# 04_Power_Supply.net
KiCad netlist of a schematic drawn in Altium Designer
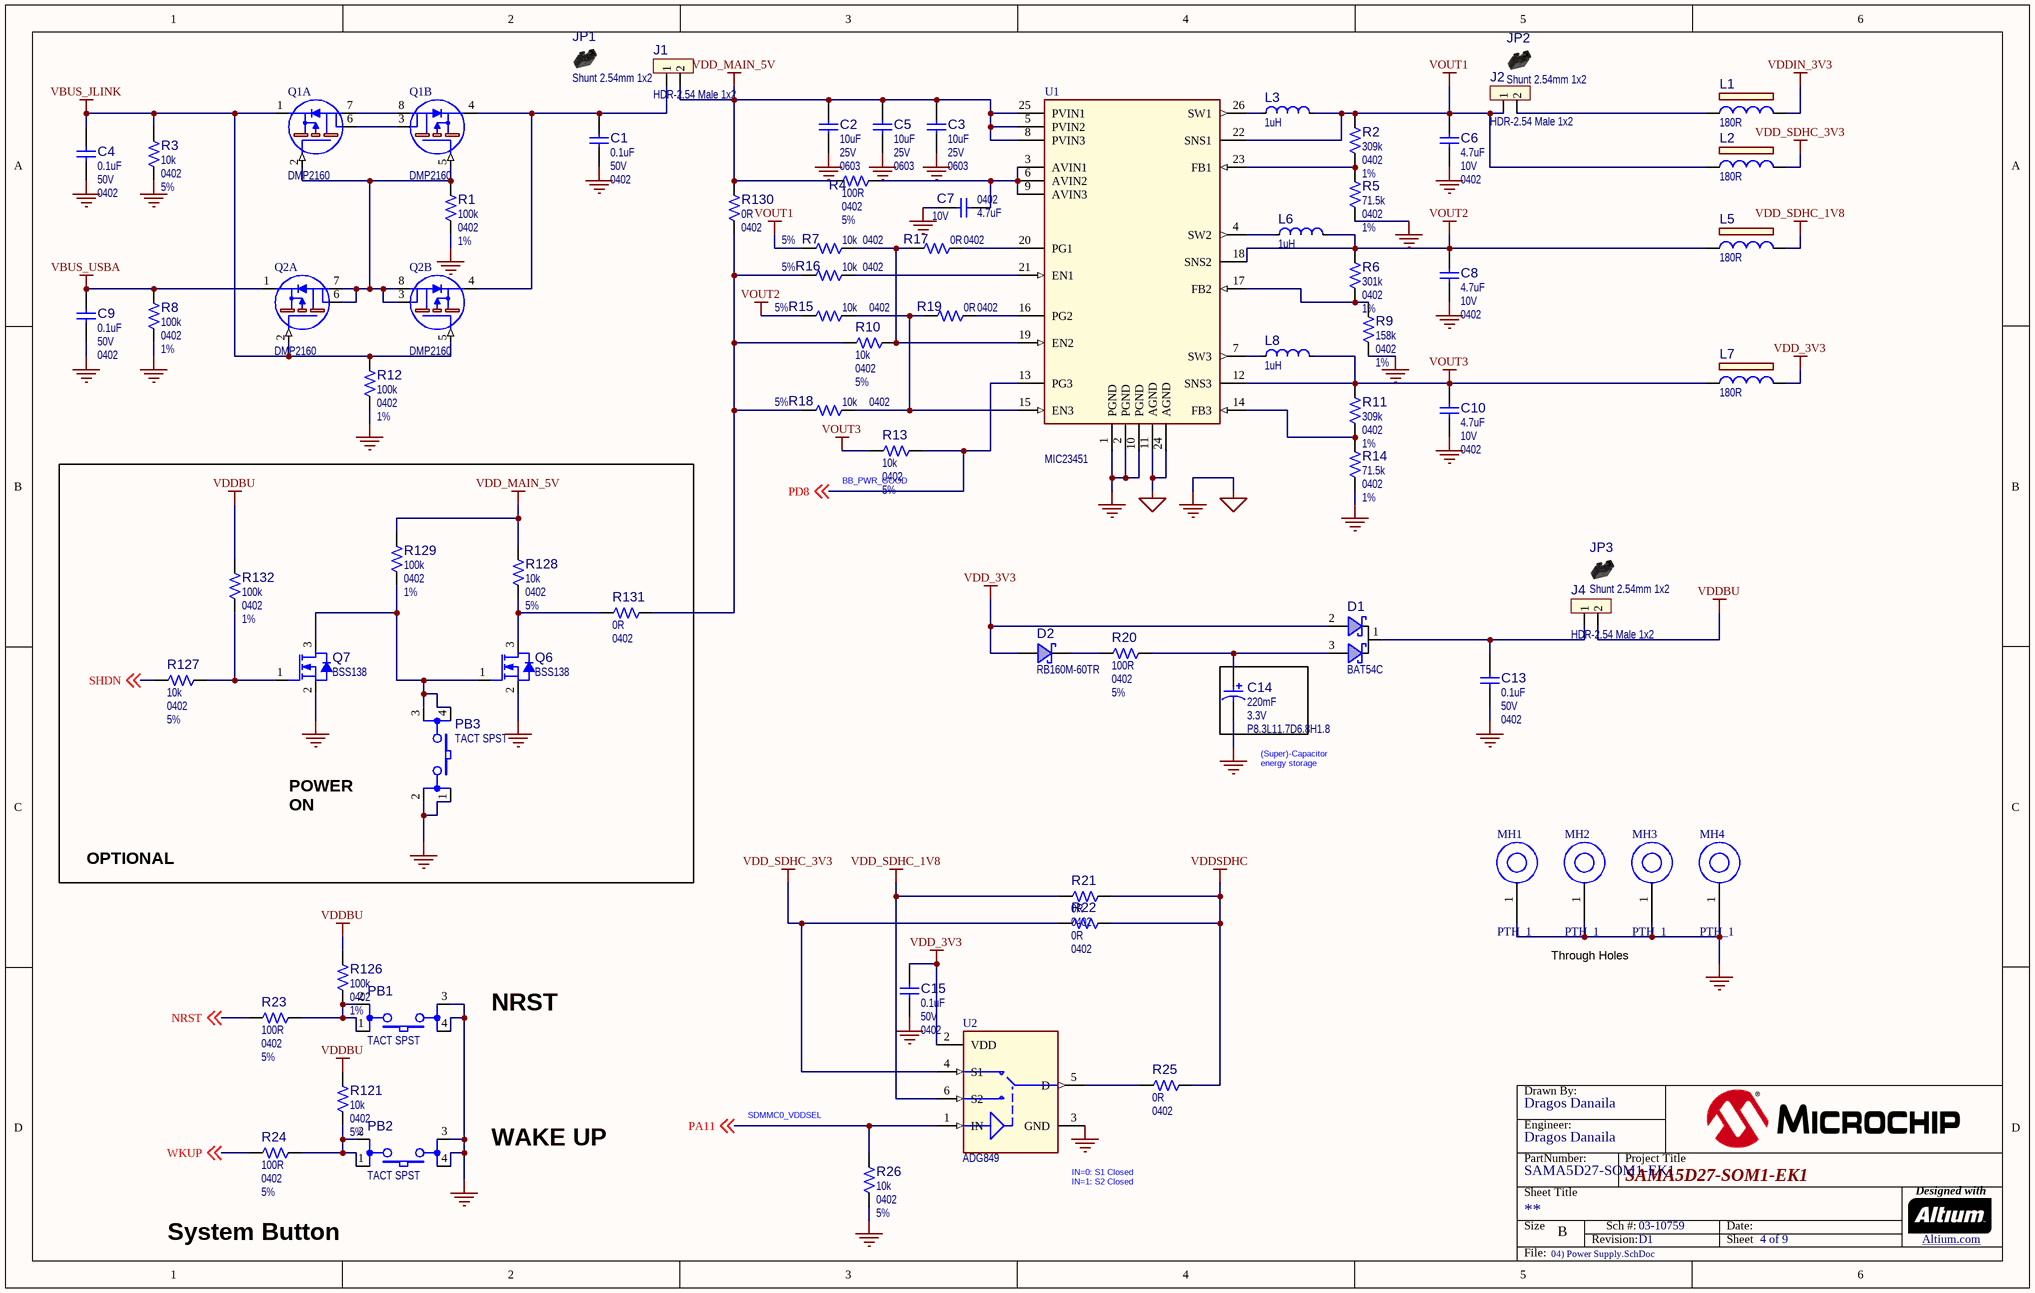
[diagram p0: 04) Power Supply.SchDoc]

(export (version "E")
  (design (tool "Eeschema 10.0.6"))
  (components
    (comp (ref "C1")
      (value "0.1uF")
      (footprint "CAP_C_0402")
      (description "Capacitor")
      (fields
        (field (name "VOLTAGE") "50V")
        (field (name "PACKAGE") "0402")
        (field (name "TOLERANCE") "10%")
        (field (name "Comment") "Capacitor NP")
        (field (name "OWNER") "Jamus Griego")
      )
      (libsource (lib "MCHP-CDB") (part "Capacitor NP"))
    )
    (comp (ref "C2")
      (value "10uF")
      (footprint "CAP_C_0603")
      (description "Capacitor")
      (fields
        (field (name "VOLTAGE") "25V")
        (field (name "PACKAGE") "0603")
        (field (name "TOLERANCE") "20%")
        (field (name "Comment") "Capacitor NP")
        (field (name "OWNER") "Razvan Cristescu")
      )
      (libsource (lib "MCHP-CDB") (part "Capacitor NP"))
    )
    (comp (ref "C3")
      (value "10uF")
      (footprint "CAP_C_0603")
      (description "Capacitor")
      (fields
        (field (name "VOLTAGE") "25V")
        (field (name "PACKAGE") "0603")
        (field (name "TOLERANCE") "20%")
        (field (name "Comment") "Capacitor NP")
        (field (name "OWNER") "Razvan Cristescu")
      )
      (libsource (lib "MCHP-CDB") (part "Capacitor NP"))
    )
    (comp (ref "C4")
      (value "0.1uF")
      (footprint "CAP_C_0402")
      (description "Capacitor")
      (fields
        (field (name "VOLTAGE") "50V")
        (field (name "PACKAGE") "0402")
        (field (name "TOLERANCE") "10%")
        (field (name "Comment") "Capacitor NP")
        (field (name "OWNER") "Jamus Griego")
      )
      (libsource (lib "MCHP-CDB") (part "Capacitor NP"))
    )
    (comp (ref "C5")
      (value "10uF")
      (footprint "CAP_C_0603")
      (description "Capacitor")
      (fields
        (field (name "VOLTAGE") "25V")
        (field (name "PACKAGE") "0603")
        (field (name "TOLERANCE") "20%")
        (field (name "Comment") "Capacitor NP")
        (field (name "OWNER") "Razvan Cristescu")
      )
      (libsource (lib "MCHP-CDB") (part "Capacitor NP"))
    )
    (comp (ref "C6")
      (value "4.7uF")
      (footprint "CAP_C_0402")
      (description "Capacitor")
      (fields
        (field (name "VOLTAGE") "10V")
        (field (name "PACKAGE") "0402")
        (field (name "TOLERANCE") "10%")
        (field (name "Comment") "Capacitor NP")
        (field (name "OWNER") "Jesus Aviles")
      )
      (libsource (lib "MCHP-CDB") (part "Capacitor NP"))
    )
    (comp (ref "C7")
      (value "4.7uF")
      (footprint "CAP_C_0402")
      (description "Capacitor")
      (fields
        (field (name "VOLTAGE") "10V")
        (field (name "PACKAGE") "0402")
        (field (name "TOLERANCE") "10%")
        (field (name "Comment") "Capacitor NP")
        (field (name "OWNER") "Jesus Aviles")
      )
      (libsource (lib "MCHP-CDB") (part "Capacitor NP"))
    )
    (comp (ref "C8")
      (value "4.7uF")
      (footprint "CAP_C_0402")
      (description "Capacitor")
      (fields
        (field (name "VOLTAGE") "10V")
        (field (name "PACKAGE") "0402")
        (field (name "TOLERANCE") "10%")
        (field (name "Comment") "Capacitor NP")
        (field (name "OWNER") "Jesus Aviles")
      )
      (libsource (lib "MCHP-CDB") (part "Capacitor NP"))
    )
    (comp (ref "C9")
      (value "0.1uF")
      (footprint "CAP_C_0402")
      (description "Capacitor")
      (fields
        (field (name "VOLTAGE") "50V")
        (field (name "PACKAGE") "0402")
        (field (name "TOLERANCE") "10%")
        (field (name "Comment") "Capacitor NP")
        (field (name "OWNER") "Jamus Griego")
      )
      (libsource (lib "MCHP-CDB") (part "Capacitor NP"))
    )
    (comp (ref "C10")
      (value "4.7uF")
      (footprint "CAP_C_0402")
      (description "Capacitor")
      (fields
        (field (name "VOLTAGE") "10V")
        (field (name "PACKAGE") "0402")
        (field (name "TOLERANCE") "10%")
        (field (name "Comment") "Capacitor NP")
        (field (name "OWNER") "Jesus Aviles")
      )
      (libsource (lib "MCHP-CDB") (part "Capacitor NP"))
    )
    (comp (ref "C13")
      (value "0.1uF")
      (footprint "CAP_C_0402")
      (description "Capacitor")
      (fields
        (field (name "VOLTAGE") "50V")
        (field (name "PACKAGE") "0402")
        (field (name "TOLERANCE") "10%")
        (field (name "Comment") "Capacitor NP")
        (field (name "OWNER") "Jamus Griego")
      )
      (libsource (lib "MCHP-CDB") (part "Capacitor NP"))
    )
    (comp (ref "C14")
      (value "220mF")
      (footprint "CAP_AX_P8.3L11.7D6.8H1.8")
      (description "Capacitor")
      (fields
        (field (name "VOLTAGE") "3.3V")
        (field (name "PACKAGE") "P8.3L11.7D6.8H1.8")
        (field (name "TOLERANCE") "-20%, +80%")
        (field (name "Comment") "Capacitor POL")
        (field (name "OWNER") "Alexandru Chiser - M19201")
      )
      (libsource (lib "MCHP-CDB") (part "Capacitor POL"))
    )
    (comp (ref "C15")
      (value "0.1uF")
      (footprint "CAP_C_0402")
      (description "Capacitor")
      (fields
        (field (name "VOLTAGE") "50V")
        (field (name "PACKAGE") "0402")
        (field (name "TOLERANCE") "10%")
        (field (name "Comment") "Capacitor NP")
        (field (name "OWNER") "Jamus Griego")
      )
      (libsource (lib "MCHP-CDB") (part "Capacitor NP"))
    )
    (comp (ref "D1")
      (value "BAT54C")
      (footprint "SOT-23-3_REVERSED")
      (fields (field (name "POWER") "330mW") (field (name "Comment") "Diode Schottky Dual CK-1"))
      (libsource (lib "MCHP-CDB") (part "Diode Schottky Dual CK-1"))
    )
    (comp (ref "D2")
      (value "RB160M-60TR")
      (footprint "SOD-123FL")
      (description "DIO SCTKY RB160M-60TR 550mV 1A 60V SMD SOD-123F")
      (fields
        (field (name "POWER") "1W")
        (field (name "Comment") "Diode Schottky")
        (field (name "OWNER") "Dragos Danaila")
      )
      (libsource (lib "MCHP-CDB") (part "Diode Schottky"))
    )
    (comp (ref "J1")
      (value "HDR-2.54 Male 1x2")
      (footprint "HDR_M_2.54_1x2")
      (fields (field (name "Comment") "Header 1x2") (field (name "OWNER") "Bogdan P (M91398)"))
      (libsource (lib "MCHP-CDB") (part "Header 1x2"))
    )
    (comp (ref "J2")
      (value "HDR-2.54 Male 1x2")
      (footprint "HDR_M_2.54_1x2")
      (fields (field (name "Comment") "Header 1x2") (field (name "OWNER") "Bogdan P (M91398)"))
      (libsource (lib "MCHP-CDB") (part "Header 1x2"))
    )
    (comp (ref "J4")
      (value "HDR-2.54 Male 1x2")
      (footprint "HDR_M_2.54_1x2")
      (fields (field (name "Comment") "Header 1x2") (field (name "OWNER") "Bogdan P (M91398)"))
      (libsource (lib "MCHP-CDB") (part "Header 1x2"))
    )
    (comp (ref "JP1")
      (value "Shunt 2.54mm 1x2")
      (footprint "Jumper_Mechanical")
      (fields (field (name "Comment") "Jumper Mechanical") (field (name "OWNER") "Mike Ragsdale"))
      (libsource (lib "MCHP-CDB") (part "Jumper Mechanical"))
    )
    (comp (ref "JP2")
      (value "Shunt 2.54mm 1x2")
      (footprint "Jumper_Mechanical")
      (fields (field (name "Comment") "Jumper Mechanical") (field (name "OWNER") "Mike Ragsdale"))
      (libsource (lib "MCHP-CDB") (part "Jumper Mechanical"))
    )
    (comp (ref "JP3")
      (value "Shunt 2.54mm 1x2")
      (footprint "Jumper_Mechanical")
      (fields (field (name "Comment") "Jumper Mechanical") (field (name "OWNER") "Mike Ragsdale"))
      (libsource (lib "MCHP-CDB") (part "Jumper Mechanical"))
    )
    (comp (ref "L1")
      (value "180R")
      (footprint "IND_C_0603")
      (description "FERRITE 180R 1.5A SMD 0603")
      (fields (field (name "Comment") "Ferrite Bead") (field (name "OWNER") "Dragos Danaila"))
      (libsource (lib "MCHP-CDB") (part "Ferrite Bead"))
    )
    (comp (ref "L2")
      (value "180R")
      (footprint "IND_C_0603")
      (description "FERRITE 180R 1.5A SMD 0603")
      (fields (field (name "Comment") "Ferrite Bead") (field (name "OWNER") "Dragos Danaila"))
      (libsource (lib "MCHP-CDB") (part "Ferrite Bead"))
    )
    (comp (ref "L3")
      (value "1uH")
      (footprint "IND_C_1210")
      (description "Inductor")
      (fields (field (name "OWNER") "Dragos Danaila"))
      (libsource (lib "MCHP-CDB") (part "Inductor"))
    )
    (comp (ref "L5")
      (value "180R")
      (footprint "IND_C_0603")
      (description "FERRITE 180R 1.5A SMD 0603")
      (fields (field (name "Comment") "Ferrite Bead") (field (name "OWNER") "Dragos Danaila"))
      (libsource (lib "MCHP-CDB") (part "Ferrite Bead"))
    )
    (comp (ref "L6")
      (value "1uH")
      (footprint "IND_C_1210")
      (description "Inductor")
      (fields (field (name "OWNER") "Dragos Danaila"))
      (libsource (lib "MCHP-CDB") (part "Inductor"))
    )
    (comp (ref "L7")
      (value "180R")
      (footprint "IND_C_0603")
      (description "FERRITE 180R 1.5A SMD 0603")
      (fields (field (name "Comment") "Ferrite Bead") (field (name "OWNER") "Dragos Danaila"))
      (libsource (lib "MCHP-CDB") (part "Ferrite Bead"))
    )
    (comp (ref "L8")
      (value "1uH")
      (footprint "IND_C_1210")
      (description "Inductor")
      (fields (field (name "OWNER") "Dragos Danaila"))
      (libsource (lib "MCHP-CDB") (part "Inductor"))
    )
    (comp (ref "MH1")
      (value "PTH_1")
      (footprint "ATM1099C-0627-ssy-1.brd:HOLE2")
      (libsource (lib "SAMA5D27-SOM1-EK1_ REVB_Library") (part "PTH_1"))
    )
    (comp (ref "MH2")
      (value "PTH_1")
      (footprint "ATM1099C-0627-ssy-1.brd:HOLE2")
      (libsource (lib "SAMA5D27-SOM1-EK1_ REVB_Library") (part "PTH_1"))
    )
    (comp (ref "MH3")
      (value "PTH_1")
      (footprint "ATM1099C-0627-ssy-1.brd:HOLE2")
      (libsource (lib "SAMA5D27-SOM1-EK1_ REVB_Library") (part "PTH_1"))
    )
    (comp (ref "MH4")
      (value "PTH_1")
      (footprint "ATM1099C-0627-ssy-1.brd:HOLE2")
      (libsource (lib "SAMA5D27-SOM1-EK1_ REVB_Library") (part "PTH_1"))
    )
    (comp (ref "PB1")
      (value "TACT SPST")
      (footprint "SW_SMD_6mmX6mm_TL3301")
      (description "Switch")
      (fields (field (name "VOLTAGE") "12V") (field (name "Comment") "Switch 4 Pin"))
      (libsource (lib "MCHP-CDB") (part "Switch 4 Pin"))
    )
    (comp (ref "PB2")
      (value "TACT SPST")
      (footprint "SW_SMD_6mmX6mm_TL3301")
      (description "Switch")
      (fields (field (name "VOLTAGE") "12V") (field (name "Comment") "Switch 4 Pin"))
      (libsource (lib "MCHP-CDB") (part "Switch 4 Pin"))
    )
    (comp (ref "PB3")
      (value "TACT SPST")
      (footprint "SW_SMD_6mmX6mm_TL3301")
      (description "Switch")
      (fields (field (name "VOLTAGE") "12V") (field (name "Comment") "Switch 4 Pin"))
      (libsource (lib "MCHP-CDB") (part "Switch 4 Pin"))
    )
    (comp (ref "Q1")
      (value "DMP2160")
      (footprint "U-DFN2020-6_2.0x2.0")
      (description "Dual P-Channel MOSFET")
      (fields
        (field (name "POWER") "1.4W")
        (field (name "VOLTAGE") "20V")
        (field (name "OWNER") "Dragos Danaila")
      )
      (libsource (lib "") (part "Transistor U-DFN2020-6-SGDSGD_1"))
    )
    (comp (ref "Q2")
      (value "DMP2160")
      (footprint "U-DFN2020-6_2.0x2.0")
      (description "Dual P-Channel MOSFET")
      (fields
        (field (name "POWER") "1.4W")
        (field (name "VOLTAGE") "20V")
        (field (name "OWNER") "Dragos Danaila")
      )
      (libsource (lib "MCHP-CDB") (part "Transistor U-DFN2020-6-SGDSGD"))
    )
    (comp (ref "Q6")
      (value "BSS138")
      (footprint "SOT-23-3")
      (description "Transistor MOS")
      (fields
        (field (name "POWER") "360mW")
        (field (name "VOLTAGE") "50V")
        (field (name "OWNER") "Razvan Cristescu")
      )
      (libsource (lib "MCHP-CDB") (part "Transistor MOS-N GSD"))
    )
    (comp (ref "Q7")
      (value "BSS138")
      (footprint "SOT-23-3")
      (description "Transistor MOS")
      (fields
        (field (name "POWER") "360mW")
        (field (name "VOLTAGE") "50V")
        (field (name "OWNER") "Razvan Cristescu")
      )
      (libsource (lib "MCHP-CDB") (part "Transistor MOS-N GSD"))
    )
    (comp (ref "R1")
      (value "100k")
      (footprint "RES_C_0402")
      (description "Resistor")
      (fields
        (field (name "PACKAGE") "0402")
        (field (name "TOLERANCE") "1%")
        (field (name "VOLTAGE") "50V")
        (field (name "POWER") "1/10W")
        (field (name "OWNER") "Tad Ahlvers")
      )
      (libsource (lib "MCHP-CDB") (part "Resistor"))
    )
    (comp (ref "R2")
      (value "309k")
      (footprint "RES_C_0402")
      (description "Resistor")
      (fields
        (field (name "PACKAGE") "0402")
        (field (name "TOLERANCE") "1%")
        (field (name "VOLTAGE") "50V")
        (field (name "POWER") "1/16W")
        (field (name "OWNER") "Dragos Danaila")
      )
      (libsource (lib "MCHP-CDB") (part "Resistor"))
    )
    (comp (ref "R3")
      (value "10k")
      (footprint "RES_C_0402")
      (description "Resistor")
      (fields
        (field (name "PACKAGE") "0402")
        (field (name "TOLERANCE") "5%")
        (field (name "VOLTAGE") "50V")
        (field (name "POWER") "1/16W")
      )
      (libsource (lib "MCHP-CDB") (part "Resistor"))
    )
    (comp (ref "R4")
      (value "100R")
      (footprint "RES_C_0402")
      (description "Resistor")
      (fields
        (field (name "PACKAGE") "0402")
        (field (name "TOLERANCE") "5%")
        (field (name "VOLTAGE") "50V")
        (field (name "POWER") "1/16W")
        (field (name "OWNER") "Sompoch Loboonlert")
      )
      (libsource (lib "MCHP-CDB") (part "Resistor"))
    )
    (comp (ref "R5")
      (value "71.5k")
      (footprint "RES_C_0402")
      (description "Resistor")
      (fields
        (field (name "PACKAGE") "0402")
        (field (name "TOLERANCE") "1%")
        (field (name "VOLTAGE") "50V")
        (field (name "POWER") "1/16W")
        (field (name "OWNER") "Dragos Danaila")
      )
      (libsource (lib "MCHP-CDB") (part "Resistor"))
    )
    (comp (ref "R6")
      (value "301k")
      (footprint "RES_C_0402")
      (description "Resistor")
      (fields
        (field (name "PACKAGE") "0402")
        (field (name "TOLERANCE") "1%")
        (field (name "VOLTAGE") "50")
        (field (name "POWER") "1/16W")
        (field (name "OWNER") "Dragos Danaila")
      )
      (libsource (lib "MCHP-CDB") (part "Resistor"))
    )
    (comp (ref "R7")
      (value "10k")
      (footprint "RES_C_0402")
      (description "Resistor")
      (fields
        (field (name "PACKAGE") "0402")
        (field (name "TOLERANCE") "5%")
        (field (name "VOLTAGE") "50V")
        (field (name "POWER") "1/16W")
      )
      (libsource (lib "MCHP-CDB") (part "Resistor"))
    )
    (comp (ref "R8")
      (value "100k")
      (footprint "RES_C_0402")
      (description "Resistor")
      (fields
        (field (name "PACKAGE") "0402")
        (field (name "TOLERANCE") "1%")
        (field (name "VOLTAGE") "50V")
        (field (name "POWER") "1/10W")
        (field (name "OWNER") "Tad Ahlvers")
      )
      (libsource (lib "MCHP-CDB") (part "Resistor"))
    )
    (comp (ref "R9")
      (value "158k")
      (footprint "RES_C_0402")
      (description "Resistor")
      (fields
        (field (name "PACKAGE") "0402")
        (field (name "TOLERANCE") "1%")
        (field (name "VOLTAGE") "50V")
        (field (name "POWER") "1/16W")
        (field (name "OWNER") "Dragos Danaila")
      )
      (libsource (lib "MCHP-CDB") (part "Resistor"))
    )
    (comp (ref "R10")
      (value "10k")
      (footprint "RES_C_0402")
      (description "Resistor")
      (fields
        (field (name "PACKAGE") "0402")
        (field (name "TOLERANCE") "5%")
        (field (name "VOLTAGE") "50V")
        (field (name "POWER") "1/16W")
      )
      (libsource (lib "MCHP-CDB") (part "Resistor"))
    )
    (comp (ref "R11")
      (value "309k")
      (footprint "RES_C_0402")
      (description "Resistor")
      (fields
        (field (name "PACKAGE") "0402")
        (field (name "TOLERANCE") "1%")
        (field (name "VOLTAGE") "50V")
        (field (name "POWER") "1/16W")
        (field (name "OWNER") "Dragos Danaila")
      )
      (libsource (lib "MCHP-CDB") (part "Resistor"))
    )
    (comp (ref "R12")
      (value "100k")
      (footprint "RES_C_0402")
      (description "Resistor")
      (fields
        (field (name "PACKAGE") "0402")
        (field (name "TOLERANCE") "1%")
        (field (name "VOLTAGE") "50V")
        (field (name "POWER") "1/10W")
        (field (name "OWNER") "Tad Ahlvers")
      )
      (libsource (lib "MCHP-CDB") (part "Resistor"))
    )
    (comp (ref "R13")
      (value "10k")
      (footprint "RES_C_0402")
      (description "Resistor")
      (fields
        (field (name "PACKAGE") "0402")
        (field (name "TOLERANCE") "5%")
        (field (name "VOLTAGE") "50V")
        (field (name "POWER") "1/16W")
      )
      (libsource (lib "MCHP-CDB") (part "Resistor"))
    )
    (comp (ref "R14")
      (value "71.5k")
      (footprint "RES_C_0402")
      (description "Resistor")
      (fields
        (field (name "PACKAGE") "0402")
        (field (name "TOLERANCE") "1%")
        (field (name "VOLTAGE") "50V")
        (field (name "POWER") "1/16W")
        (field (name "OWNER") "Dragos Danaila")
      )
      (libsource (lib "MCHP-CDB") (part "Resistor"))
    )
    (comp (ref "R15")
      (value "10k")
      (footprint "RES_C_0402")
      (description "Resistor")
      (fields
        (field (name "PACKAGE") "0402")
        (field (name "TOLERANCE") "5%")
        (field (name "VOLTAGE") "50V")
        (field (name "POWER") "1/16W")
      )
      (libsource (lib "MCHP-CDB") (part "Resistor"))
    )
    (comp (ref "R16")
      (value "10k")
      (footprint "RES_C_0402")
      (description "Resistor")
      (fields
        (field (name "PACKAGE") "0402")
        (field (name "TOLERANCE") "5%")
        (field (name "VOLTAGE") "50V")
        (field (name "POWER") "1/16W")
      )
      (libsource (lib "MCHP-CDB") (part "Resistor"))
    )
    (comp (ref "R17")
      (value "0R")
      (footprint "RES_C_0402")
      (description "Resistor")
      (fields (field (name "PACKAGE") "0402") (field (name "POWER") "1/10W"))
      (libsource (lib "MCHP-CDB") (part "Resistor"))
    )
    (comp (ref "R18")
      (value "10k")
      (footprint "RES_C_0402")
      (description "Resistor")
      (fields
        (field (name "PACKAGE") "0402")
        (field (name "TOLERANCE") "5%")
        (field (name "VOLTAGE") "50V")
        (field (name "POWER") "1/16W")
      )
      (libsource (lib "MCHP-CDB") (part "Resistor"))
    )
    (comp (ref "R19")
      (value "0R")
      (footprint "RES_C_0402")
      (description "Resistor")
      (fields (field (name "PACKAGE") "0402") (field (name "POWER") "1/10W"))
      (libsource (lib "MCHP-CDB") (part "Resistor"))
    )
    (comp (ref "R20")
      (value "100R")
      (footprint "RES_C_0402")
      (description "Resistor")
      (fields
        (field (name "PACKAGE") "0402")
        (field (name "TOLERANCE") "5%")
        (field (name "VOLTAGE") "50V")
        (field (name "POWER") "1/16W")
        (field (name "OWNER") "Sompoch Loboonlert")
      )
      (libsource (lib "MCHP-CDB") (part "Resistor"))
    )
    (comp (ref "R21")
      (value "0R")
      (footprint "RES_C_0402")
      (description "Resistor")
      (fields (field (name "PACKAGE") "0402") (field (name "POWER") "1/10W"))
      (libsource (lib "MCHP-CDB") (part "Resistor"))
    )
    (comp (ref "R22")
      (value "0R")
      (footprint "RES_C_0402")
      (description "Resistor")
      (fields (field (name "PACKAGE") "0402") (field (name "POWER") "1/10W"))
      (libsource (lib "MCHP-CDB") (part "Resistor"))
    )
    (comp (ref "R23")
      (value "100R")
      (footprint "RES_C_0402")
      (description "Resistor")
      (fields
        (field (name "PACKAGE") "0402")
        (field (name "TOLERANCE") "5%")
        (field (name "VOLTAGE") "50V")
        (field (name "POWER") "1/16W")
        (field (name "OWNER") "Sompoch Loboonlert")
      )
      (libsource (lib "MCHP-CDB") (part "Resistor"))
    )
    (comp (ref "R24")
      (value "100R")
      (footprint "RES_C_0402")
      (description "Resistor")
      (fields
        (field (name "PACKAGE") "0402")
        (field (name "TOLERANCE") "5%")
        (field (name "VOLTAGE") "50V")
        (field (name "POWER") "1/16W")
        (field (name "OWNER") "Sompoch Loboonlert")
      )
      (libsource (lib "MCHP-CDB") (part "Resistor"))
    )
    (comp (ref "R25")
      (value "0R")
      (footprint "RES_C_0402")
      (description "Resistor")
      (fields (field (name "PACKAGE") "0402") (field (name "POWER") "1/10W"))
      (libsource (lib "MCHP-CDB") (part "Resistor"))
    )
    (comp (ref "R26")
      (value "10k")
      (footprint "RES_C_0402")
      (description "Resistor")
      (fields
        (field (name "PACKAGE") "0402")
        (field (name "TOLERANCE") "5%")
        (field (name "VOLTAGE") "50V")
        (field (name "POWER") "1/16W")
      )
      (libsource (lib "MCHP-CDB") (part "Resistor"))
    )
    (comp (ref "R121")
      (value "10k")
      (footprint "RES_C_0402")
      (description "Resistor")
      (fields
        (field (name "PACKAGE") "0402")
        (field (name "TOLERANCE") "5%")
        (field (name "VOLTAGE") "50V")
        (field (name "POWER") "1/16W")
      )
      (libsource (lib "MCHP-CDB") (part "Resistor"))
    )
    (comp (ref "R126")
      (value "100k")
      (footprint "RES_C_0402")
      (description "Resistor")
      (fields
        (field (name "PACKAGE") "0402")
        (field (name "TOLERANCE") "1%")
        (field (name "VOLTAGE") "50V")
        (field (name "POWER") "1/10W")
        (field (name "OWNER") "Tad Ahlvers")
      )
      (libsource (lib "MCHP-CDB") (part "Resistor"))
    )
    (comp (ref "R127")
      (value "10k")
      (footprint "RES_C_0402")
      (description "Resistor")
      (fields
        (field (name "PACKAGE") "0402")
        (field (name "TOLERANCE") "5%")
        (field (name "VOLTAGE") "50V")
        (field (name "POWER") "1/16W")
      )
      (libsource (lib "MCHP-CDB") (part "Resistor"))
    )
    (comp (ref "R128")
      (value "10k")
      (footprint "RES_C_0402")
      (description "Resistor")
      (fields
        (field (name "PACKAGE") "0402")
        (field (name "TOLERANCE") "5%")
        (field (name "VOLTAGE") "50V")
        (field (name "POWER") "1/16W")
      )
      (libsource (lib "MCHP-CDB") (part "Resistor"))
    )
    (comp (ref "R129")
      (value "100k")
      (footprint "RES_C_0402")
      (description "Resistor")
      (fields
        (field (name "PACKAGE") "0402")
        (field (name "TOLERANCE") "1%")
        (field (name "VOLTAGE") "50V")
        (field (name "POWER") "1/10W")
        (field (name "OWNER") "Tad Ahlvers")
      )
      (libsource (lib "MCHP-CDB") (part "Resistor"))
    )
    (comp (ref "R130")
      (value "0R")
      (footprint "RES_C_0402")
      (description "Resistor")
      (fields (field (name "PACKAGE") "0402") (field (name "POWER") "1/10W"))
      (libsource (lib "MCHP-CDB") (part "Resistor"))
    )
    (comp (ref "R131")
      (value "0R")
      (footprint "RES_C_0402")
      (description "Resistor")
      (fields (field (name "PACKAGE") "0402") (field (name "POWER") "1/10W"))
      (libsource (lib "MCHP-CDB") (part "Resistor"))
    )
    (comp (ref "R132")
      (value "100k")
      (footprint "RES_C_0402")
      (description "Resistor")
      (fields
        (field (name "PACKAGE") "0402")
        (field (name "TOLERANCE") "1%")
        (field (name "VOLTAGE") "50V")
        (field (name "POWER") "1/10W")
        (field (name "OWNER") "Tad Ahlvers")
      )
      (libsource (lib "MCHP-CDB") (part "Resistor"))
    )
    (comp (ref "U1")
      (value "MIC23451")
      (footprint "VQFN-26_4X4_MIC23451")
      (description "MCHP ANALOG SWITCHER Buck 1V MIC23451-AAAYFL VQFN-26")
      (fields (field (name "Comment") "MIC23451 VQFN-26") (field (name "OWNER") "Razvan Cristescu"))
      (libsource (lib "MCHP-CDB") (part "MIC23451 VQFN-26"))
    )
    (comp (ref "U2")
      (value "ADG849")
      (footprint "SC-70-6")
      (description "IC SWITCHER ADG849 Analog Switch SC70")
      (fields (field (name "Comment") "ADG849 SC70") (field (name "OWNER") "Dragos Danaila"))
      (libsource (lib "MCHP-CDB") (part "ADG849 SC70"))
    )
  )
  (nets
    (net (code "1") (name "GND_POWER") (class "Default")
      (node (ref "C1") (pin "2") (pinfunction "2_2") (pintype "passive"))
      (node (ref "C10") (pin "2") (pinfunction "2_2") (pintype "passive"))
      (node (ref "C13") (pin "2") (pinfunction "2_2") (pintype "passive"))
      (node (ref "C14") (pin "2") (pinfunction "2_2") (pintype "passive"))
      (node (ref "C15") (pin "2") (pinfunction "2_2") (pintype "passive"))
      (node (ref "C2") (pin "2") (pinfunction "2_2") (pintype "passive"))
      (node (ref "C3") (pin "2") (pinfunction "2_2") (pintype "passive"))
      (node (ref "C4") (pin "2") (pinfunction "2_2") (pintype "passive"))
      (node (ref "C5") (pin "2") (pinfunction "2_2") (pintype "passive"))
      (node (ref "C6") (pin "2") (pinfunction "2_2") (pintype "passive"))
      (node (ref "C7") (pin "2") (pinfunction "2_2") (pintype "passive"))
      (node (ref "C8") (pin "2") (pinfunction "2_2") (pintype "passive"))
      (node (ref "C9") (pin "2") (pinfunction "2_2") (pintype "passive"))
      (node (ref "MH1") (pin "1") (pinfunction "1_1") (pintype "passive"))
      (node (ref "MH2") (pin "1") (pinfunction "1_1") (pintype "passive"))
      (node (ref "MH3") (pin "1") (pinfunction "1_1") (pintype "passive"))
      (node (ref "MH4") (pin "1") (pinfunction "1_1") (pintype "passive"))
      (node (ref "PB1") (pin "3") (pinfunction "3_3") (pintype "passive"))
      (node (ref "PB1") (pin "4") (pinfunction "4_4") (pintype "passive"))
      (node (ref "PB2") (pin "3") (pinfunction "3_3") (pintype "passive"))
      (node (ref "PB2") (pin "4") (pinfunction "4_4") (pintype "passive"))
      (node (ref "PB3") (pin "1") (pinfunction "1_1") (pintype "passive"))
      (node (ref "PB3") (pin "2") (pinfunction "2_2") (pintype "passive"))
      (node (ref "Q6") (pin "2") (pinfunction "S_2") (pintype "passive"))
      (node (ref "Q7") (pin "2") (pinfunction "S_2") (pintype "passive"))
      (node (ref "R1") (pin "2") (pinfunction "2_2") (pintype "passive"))
      (node (ref "R12") (pin "2") (pinfunction "2_2") (pintype "passive"))
      (node (ref "R14") (pin "2") (pinfunction "2_2") (pintype "passive"))
      (node (ref "R26") (pin "1") (pinfunction "1_1") (pintype "passive"))
      (node (ref "R3") (pin "1") (pinfunction "1_1") (pintype "passive"))
      (node (ref "R5") (pin "2") (pinfunction "2_2") (pintype "passive"))
      (node (ref "R8") (pin "2") (pinfunction "2_2") (pintype "passive"))
      (node (ref "R9") (pin "2") (pinfunction "2_2") (pintype "passive"))
      (node (ref "U1") (pin "1") (pinfunction "PGND_1") (pintype "power_in"))
      (node (ref "U1") (pin "10") (pinfunction "PGND_10") (pintype "power_in"))
      (node (ref "U1") (pin "11") (pinfunction "AGND_11") (pintype "power_in"))
      (node (ref "U1") (pin "2") (pinfunction "PGND_2") (pintype "power_in"))
      (node (ref "U1") (pin "24") (pinfunction "AGND_24") (pintype "power_in"))
      (node (ref "U2") (pin "3") (pinfunction "GND_3") (pintype "power_in"))
    )
    (net (code "2") (name "NRST") (class "Default")
      (node (ref "R23") (pin "1") (pinfunction "1_1") (pintype "passive"))
    )
    (net (code "3") (name "Net-(C14-Pad1)") (class "Default")
      (node (ref "C14") (pin "1") (pinfunction "1_1") (pintype "passive"))
      (node (ref "D1") (pin "3") (pinfunction "A_3") (pintype "passive"))
      (node (ref "R20") (pin "2") (pinfunction "2_2") (pintype "passive"))
    )
    (net (code "4") (name "Net-(D1-KK)") (class "Default")
      (node (ref "C13") (pin "1") (pinfunction "1_1") (pintype "passive"))
      (node (ref "D1") (pin "1") (pinfunction "KK_1") (pintype "passive"))
      (node (ref "J4") (pin "1") (pinfunction "1_1") (pintype "passive"))
    )
    (net (code "5") (name "Net-(D2-K)") (class "Default")
      (node (ref "D2") (pin "2") (pinfunction "K_2") (pintype "passive"))
      (node (ref "R20") (pin "1") (pinfunction "1_1") (pintype "passive"))
    )
    (net (code "6") (name "Net-(J2-Pad2)") (class "Default")
      (node (ref "J2") (pin "2") (pinfunction "2_2") (pintype "passive"))
      (node (ref "L1") (pin "1") (pinfunction "1_1") (pintype "passive"))
    )
    (net (code "7") (name "Net-(L3-S)") (class "Default")
      (node (ref "L3") (pin "1") (pinfunction "S_1") (pintype "passive"))
      (node (ref "U1") (pin "26") (pinfunction "SW1_26") (pintype "output"))
    )
    (net (code "8") (name "Net-(L6-S)") (class "Default")
      (node (ref "L6") (pin "1") (pinfunction "S_1") (pintype "passive"))
      (node (ref "U1") (pin "4") (pinfunction "SW2_4") (pintype "output"))
    )
    (net (code "9") (name "Net-(L8-S)") (class "Default")
      (node (ref "L8") (pin "1") (pinfunction "S_1") (pintype "passive"))
      (node (ref "U1") (pin "7") (pinfunction "SW3_7") (pintype "output"))
    )
    (net (code "10") (name "Net-(PB1-Pad1)") (class "Default")
      (node (ref "PB1") (pin "1") (pinfunction "1_1") (pintype "passive"))
      (node (ref "PB1") (pin "2") (pinfunction "2_2") (pintype "passive"))
      (node (ref "R126") (pin "2") (pinfunction "2_2") (pintype "passive"))
      (node (ref "R23") (pin "2") (pinfunction "2_2") (pintype "passive"))
    )
    (net (code "11") (name "Net-(PB2-Pad1)") (class "Default")
      (node (ref "PB2") (pin "1") (pinfunction "1_1") (pintype "passive"))
      (node (ref "PB2") (pin "2") (pinfunction "2_2") (pintype "passive"))
      (node (ref "R121") (pin "2") (pinfunction "2_2") (pintype "passive"))
      (node (ref "R24") (pin "2") (pinfunction "2_2") (pintype "passive"))
    )
    (net (code "12") (name "Net-(Q1A-D2_1)") (class "Default")
      (node (ref "Q1") (pin "3") (pinfunction "D2_1_3") (pintype "passive"))
      (node (ref "Q1") (pin "6") (pinfunction "D2_1_6") (pintype "passive"))
    )
    (net (code "13") (name "Net-(Q1A-D2_2)") (class "Default")
      (node (ref "Q1") (pin "7") (pinfunction "D2_2_7") (pintype "passive"))
      (node (ref "Q1") (pin "8") (pinfunction "D2_2_8") (pintype "passive"))
    )
    (net (code "14") (name "Net-(Q1A-G2)") (class "Default")
      (node (ref "Q1") (pin "2") (pinfunction "G2_2") (pintype "input"))
      (node (ref "Q1") (pin "5") (pinfunction "G2_5") (pintype "input"))
      (node (ref "Q2") (pin "3") (pinfunction "D2_1_3") (pintype "passive"))
      (node (ref "Q2") (pin "6") (pinfunction "D2_1_6") (pintype "passive"))
      (node (ref "Q2") (pin "7") (pinfunction "D2_2_7") (pintype "passive"))
      (node (ref "Q2") (pin "8") (pinfunction "D2_2_8") (pintype "passive"))
      (node (ref "R1") (pin "1") (pinfunction "1_1") (pintype "passive"))
    )
    (net (code "15") (name "Net-(Q1B-S2)") (class "Default")
      (node (ref "C1") (pin "1") (pinfunction "1_1") (pintype "passive"))
      (node (ref "J1") (pin "1") (pinfunction "1_1") (pintype "passive"))
      (node (ref "Q1") (pin "4") (pinfunction "S2_4") (pintype "passive"))
      (node (ref "Q2") (pin "4") (pinfunction "S2_4") (pintype "passive"))
    )
    (net (code "16") (name "Net-(Q6-D)") (class "Default")
      (node (ref "Q6") (pin "3") (pinfunction "D_3") (pintype "passive"))
      (node (ref "R128") (pin "1") (pinfunction "1_1") (pintype "passive"))
      (node (ref "R131") (pin "1") (pinfunction "1_1") (pintype "passive"))
    )
    (net (code "17") (name "Net-(Q6-G)") (class "Default")
      (node (ref "PB3") (pin "3") (pinfunction "3_3") (pintype "passive"))
      (node (ref "PB3") (pin "4") (pinfunction "4_4") (pintype "passive"))
      (node (ref "Q6") (pin "1") (pinfunction "G_1") (pintype "passive"))
      (node (ref "Q7") (pin "3") (pinfunction "D_3") (pintype "passive"))
      (node (ref "R129") (pin "2") (pinfunction "2_2") (pintype "passive"))
    )
    (net (code "18") (name "Net-(Q7-G)") (class "Default")
      (node (ref "Q7") (pin "1") (pinfunction "G_1") (pintype "passive"))
      (node (ref "R127") (pin "2") (pinfunction "2_2") (pintype "passive"))
      (node (ref "R132") (pin "2") (pinfunction "2_2") (pintype "passive"))
    )
    (net (code "19") (name "Net-(R10-Pad1)") (class "Default")
      (node (ref "R10") (pin "1") (pinfunction "1_1") (pintype "passive"))
      (node (ref "R130") (pin "1") (pinfunction "1_1") (pintype "passive"))
      (node (ref "R131") (pin "2") (pinfunction "2_2") (pintype "passive"))
      (node (ref "R16") (pin "1") (pinfunction "1_1") (pintype "passive"))
      (node (ref "R18") (pin "2") (pinfunction "2_2") (pintype "passive"))
    )
    (net (code "20") (name "Net-(U1-AVIN1)") (class "Default")
      (node (ref "C7") (pin "1") (pinfunction "1_1") (pintype "passive"))
      (node (ref "R4") (pin "2") (pinfunction "2_2") (pintype "passive"))
      (node (ref "U1") (pin "3") (pinfunction "AVIN1_3") (pintype "power_in"))
      (node (ref "U1") (pin "6") (pinfunction "AVIN2_6") (pintype "power_in"))
      (node (ref "U1") (pin "9") (pinfunction "AVIN3_9") (pintype "power_in"))
    )
    (net (code "21") (name "Net-(U1-EN1)") (class "Default")
      (node (ref "R16") (pin "2") (pinfunction "2_2") (pintype "passive"))
      (node (ref "U1") (pin "21") (pinfunction "EN1_21") (pintype "input"))
    )
    (net (code "22") (name "Net-(U1-EN2)") (class "Default")
      (node (ref "R10") (pin "2") (pinfunction "2_2") (pintype "passive"))
      (node (ref "R17") (pin "1") (pinfunction "1_1") (pintype "passive"))
      (node (ref "R7") (pin "2") (pinfunction "2_2") (pintype "passive"))
      (node (ref "U1") (pin "19") (pinfunction "EN2_19") (pintype "input"))
    )
    (net (code "23") (name "Net-(U1-EN3)") (class "Default")
      (node (ref "R15") (pin "1") (pinfunction "1_1") (pintype "passive"))
      (node (ref "R18") (pin "1") (pinfunction "1_1") (pintype "passive"))
      (node (ref "R19") (pin "1") (pinfunction "1_1") (pintype "passive"))
      (node (ref "U1") (pin "15") (pinfunction "EN3_15") (pintype "input"))
    )
    (net (code "24") (name "Net-(U1-FB1)") (class "Default")
      (node (ref "R2") (pin "2") (pinfunction "2_2") (pintype "passive"))
      (node (ref "R5") (pin "1") (pinfunction "1_1") (pintype "passive"))
      (node (ref "U1") (pin "23") (pinfunction "FB1_23") (pintype "input"))
    )
    (net (code "25") (name "Net-(U1-FB2)") (class "Default")
      (node (ref "R6") (pin "2") (pinfunction "2_2") (pintype "passive"))
      (node (ref "R9") (pin "1") (pinfunction "1_1") (pintype "passive"))
      (node (ref "U1") (pin "17") (pinfunction "FB2_17") (pintype "input"))
    )
    (net (code "26") (name "Net-(U1-FB3)") (class "Default")
      (node (ref "R11") (pin "2") (pinfunction "2_2") (pintype "passive"))
      (node (ref "R14") (pin "1") (pinfunction "1_1") (pintype "passive"))
      (node (ref "U1") (pin "14") (pinfunction "FB3_14") (pintype "input"))
    )
    (net (code "27") (name "Net-(U1-PG1)") (class "Default")
      (node (ref "R17") (pin "2") (pinfunction "2_2") (pintype "passive"))
      (node (ref "U1") (pin "20") (pinfunction "PG1_20") (pintype "power_in"))
    )
    (net (code "28") (name "Net-(U1-PG2)") (class "Default")
      (node (ref "R19") (pin "2") (pinfunction "2_2") (pintype "passive"))
      (node (ref "U1") (pin "16") (pinfunction "PG2_16") (pintype "power_in"))
    )
    (net (code "29") (name "Net-(U2-D)") (class "Default")
      (node (ref "R25") (pin "1") (pinfunction "1_1") (pintype "passive"))
      (node (ref "U2") (pin "5") (pinfunction "D_5") (pintype "output"))
    )
    (net (code "30") (name "PA11") (class "Default")
      (node (ref "R26") (pin "2") (pinfunction "2_2") (pintype "passive"))
      (node (ref "U2") (pin "1") (pinfunction "IN_1") (pintype "input"))
    )
    (net (code "31") (name "PD8") (class "Default")
      (node (ref "R13") (pin "2") (pinfunction "2_2") (pintype "passive"))
      (node (ref "U1") (pin "13") (pinfunction "PG3_13") (pintype "power_in"))
    )
    (net (code "32") (name "SHDN") (class "Default")
      (node (ref "R127") (pin "1") (pinfunction "1_1") (pintype "passive"))
    )
    (net (code "33") (name "VBUS_JLINK") (class "Default")
      (node (ref "C4") (pin "1") (pinfunction "1_1") (pintype "passive"))
      (node (ref "Q1") (pin "1") (pinfunction "S2_1") (pintype "passive"))
      (node (ref "Q2") (pin "2") (pinfunction "G2_2") (pintype "input"))
      (node (ref "Q2") (pin "5") (pinfunction "G2_5") (pintype "input"))
      (node (ref "R12") (pin "1") (pinfunction "1_1") (pintype "passive"))
      (node (ref "R3") (pin "2") (pinfunction "2_2") (pintype "passive"))
    )
    (net (code "34") (name "VBUS_USBA") (class "Default")
      (node (ref "C9") (pin "1") (pinfunction "1_1") (pintype "passive"))
      (node (ref "Q2") (pin "1") (pinfunction "S2_1") (pintype "passive"))
      (node (ref "R8") (pin "1") (pinfunction "1_1") (pintype "passive"))
    )
    (net (code "35") (name "VDDBU") (class "Default")
      (node (ref "J4") (pin "2") (pinfunction "2_2") (pintype "passive"))
      (node (ref "R121") (pin "1") (pinfunction "1_1") (pintype "passive"))
      (node (ref "R126") (pin "1") (pinfunction "1_1") (pintype "passive"))
      (node (ref "R132") (pin "1") (pinfunction "1_1") (pintype "passive"))
    )
    (net (code "36") (name "VDDIN_3V3") (class "Default")
      (node (ref "L1") (pin "2") (pinfunction "2_2") (pintype "passive"))
    )
    (net (code "37") (name "VDDSDHC") (class "Default")
      (node (ref "R21") (pin "2") (pinfunction "2_2") (pintype "passive"))
      (node (ref "R22") (pin "2") (pinfunction "2_2") (pintype "passive"))
      (node (ref "R25") (pin "2") (pinfunction "2_2") (pintype "passive"))
    )
    (net (code "38") (name "VDD_3V3") (class "Default")
      (node (ref "C15") (pin "1") (pinfunction "1_1") (pintype "passive"))
      (node (ref "D1") (pin "2") (pinfunction "A_2") (pintype "passive"))
      (node (ref "D2") (pin "1") (pinfunction "A_1") (pintype "passive"))
      (node (ref "L7") (pin "2") (pinfunction "2_2") (pintype "passive"))
      (node (ref "U2") (pin "2") (pinfunction "VDD_2") (pintype "power_in"))
    )
    (net (code "39") (name "VDD_MAIN_5V") (class "Default")
      (node (ref "C2") (pin "1") (pinfunction "1_1") (pintype "passive"))
      (node (ref "C3") (pin "1") (pinfunction "1_1") (pintype "passive"))
      (node (ref "C5") (pin "1") (pinfunction "1_1") (pintype "passive"))
      (node (ref "J1") (pin "2") (pinfunction "2_2") (pintype "passive"))
      (node (ref "R128") (pin "2") (pinfunction "2_2") (pintype "passive"))
      (node (ref "R129") (pin "1") (pinfunction "1_1") (pintype "passive"))
      (node (ref "R130") (pin "2") (pinfunction "2_2") (pintype "passive"))
      (node (ref "R4") (pin "1") (pinfunction "1_1") (pintype "passive"))
      (node (ref "U1") (pin "25") (pinfunction "PVIN1_25") (pintype "power_in"))
      (node (ref "U1") (pin "5") (pinfunction "PVIN2_5") (pintype "power_in"))
      (node (ref "U1") (pin "8") (pinfunction "PVIN3_8") (pintype "power_in"))
    )
    (net (code "40") (name "VDD_SDHC_1V8") (class "Default")
      (node (ref "L5") (pin "2") (pinfunction "2_2") (pintype "passive"))
      (node (ref "R21") (pin "1") (pinfunction "1_1") (pintype "passive"))
      (node (ref "U2") (pin "6") (pinfunction "S2_6") (pintype "input"))
    )
    (net (code "41") (name "VDD_SDHC_3V3") (class "Default")
      (node (ref "L2") (pin "2") (pinfunction "2_2") (pintype "passive"))
      (node (ref "R22") (pin "1") (pinfunction "1_1") (pintype "passive"))
      (node (ref "U2") (pin "4") (pinfunction "S1_4") (pintype "input"))
    )
    (net (code "42") (name "VOUT1") (class "Default")
      (node (ref "C6") (pin "1") (pinfunction "1_1") (pintype "passive"))
      (node (ref "J2") (pin "1") (pinfunction "1_1") (pintype "passive"))
      (node (ref "L2") (pin "1") (pinfunction "1_1") (pintype "passive"))
      (node (ref "L3") (pin "2") (pinfunction "F_2") (pintype "passive"))
      (node (ref "R2") (pin "1") (pinfunction "1_1") (pintype "passive"))
      (node (ref "R7") (pin "1") (pinfunction "1_1") (pintype "passive"))
      (node (ref "U1") (pin "22") (pinfunction "SNS1_22") (pintype "power_in"))
    )
    (net (code "43") (name "VOUT2") (class "Default")
      (node (ref "C8") (pin "1") (pinfunction "1_1") (pintype "passive"))
      (node (ref "L5") (pin "1") (pinfunction "1_1") (pintype "passive"))
      (node (ref "L6") (pin "2") (pinfunction "F_2") (pintype "passive"))
      (node (ref "R15") (pin "2") (pinfunction "2_2") (pintype "passive"))
      (node (ref "R6") (pin "1") (pinfunction "1_1") (pintype "passive"))
      (node (ref "U1") (pin "18") (pinfunction "SNS2_18") (pintype "power_in"))
    )
    (net (code "44") (name "VOUT3") (class "Default")
      (node (ref "C10") (pin "1") (pinfunction "1_1") (pintype "passive"))
      (node (ref "L7") (pin "1") (pinfunction "1_1") (pintype "passive"))
      (node (ref "L8") (pin "2") (pinfunction "F_2") (pintype "passive"))
      (node (ref "R11") (pin "1") (pinfunction "1_1") (pintype "passive"))
      (node (ref "R13") (pin "1") (pinfunction "1_1") (pintype "passive"))
      (node (ref "U1") (pin "12") (pinfunction "SNS3_12") (pintype "power_in"))
    )
    (net (code "45") (name "WKUP") (class "Default")
      (node (ref "R24") (pin "1") (pinfunction "1_1") (pintype "passive"))
    )
  )
)
